# Power_3V3_LDO.net
KiCad netlist of a schematic drawn in Altium Designer
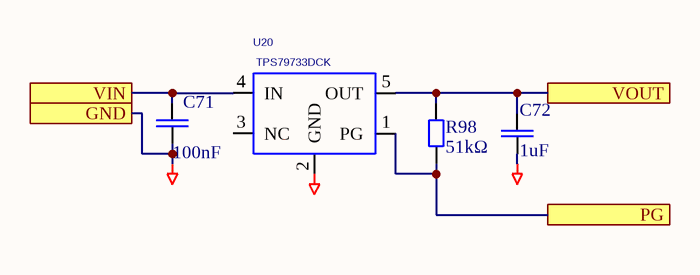
[diagram p0: Power_3V3_LDO.SchDoc]

(export (version "E")
  (design (tool "Eeschema 10.0.6"))
  (components
    (comp (ref "C71")
      (value "100nF")
      (footprint "CAPC1608N")
      (description "Generic ceramic SMD capacitor")
      (fields (field (name "MAINTAINER") "Evgeniy Kotov"))
      (libsource (lib "[Capacitors] Capacitors SMD") (part "CAPC"))
    )
    (comp (ref "C72")
      (value "1uF")
      (footprint "CAPC2012N")
      (description "Generic ceramic SMD capacitor")
      (fields (field (name "MAINTAINER") "Evgeniy Kotov"))
      (libsource (lib "[Capacitors] Capacitors SMD") (part "CAPC"))
    )
    (comp (ref "R98")
      (value "51kΩ")
      (footprint "RESC2012N")
      (description "Resistor, Generic, SMD")
      (fields (field (name "MAINTAINER") "Evgeniy Kotov"))
      (libsource (lib "[Resistors] Resistors SMD") (part "RESC"))
    )
    (comp (ref "U20")
      (value "TPS79733DCK")
      (footprint "SOT65P210X110-5N")
      (description "Ultra low power (Iq=1.2 mkA) LDO 3.3V Fixed")
      (fields (field (name "MANUFACTURER") "Texas Instruments"))
      (libsource (lib "[ICs And Semiconductors] Analog & Interface") (part "TPS79733DCK"))
    )
  )
  (nets
    (net (code "1") (name "/PG") (class "Default")
      (node (ref "R98") (pin "1") (pintype "passive"))
      (node (ref "U20") (pin "1") (pinfunction "PG_1") (pintype "passive"))
    )
    (net (code "2") (name "/VIN") (class "Default")
      (node (ref "C71") (pin "2") (pintype "passive"))
      (node (ref "U20") (pin "4") (pinfunction "IN_4") (pintype "passive"))
    )
    (net (code "3") (name "/VOUT") (class "Default")
      (node (ref "C72") (pin "2") (pintype "passive"))
      (node (ref "R98") (pin "2") (pintype "passive"))
      (node (ref "U20") (pin "5") (pinfunction "OUT_5") (pintype "power_in"))
    )
    (net (code "4") (name "GND") (class "Default")
      (node (ref "C71") (pin "1") (pintype "passive"))
      (node (ref "C72") (pin "1") (pintype "passive"))
      (node (ref "U20") (pin "2") (pinfunction "GND_2") (pintype "power_in"))
    )
    (net (code "5") (name "unconnected-(U20-NC-Pad3)") (class "Default")
      (node (ref "U20") (pin "3") (pinfunction "NC_3") (pintype "passive"))
    )
  )
)
